# USBSocket_Type4_v1_0.net
KiCad netlist of a schematic drawn in EAGLE
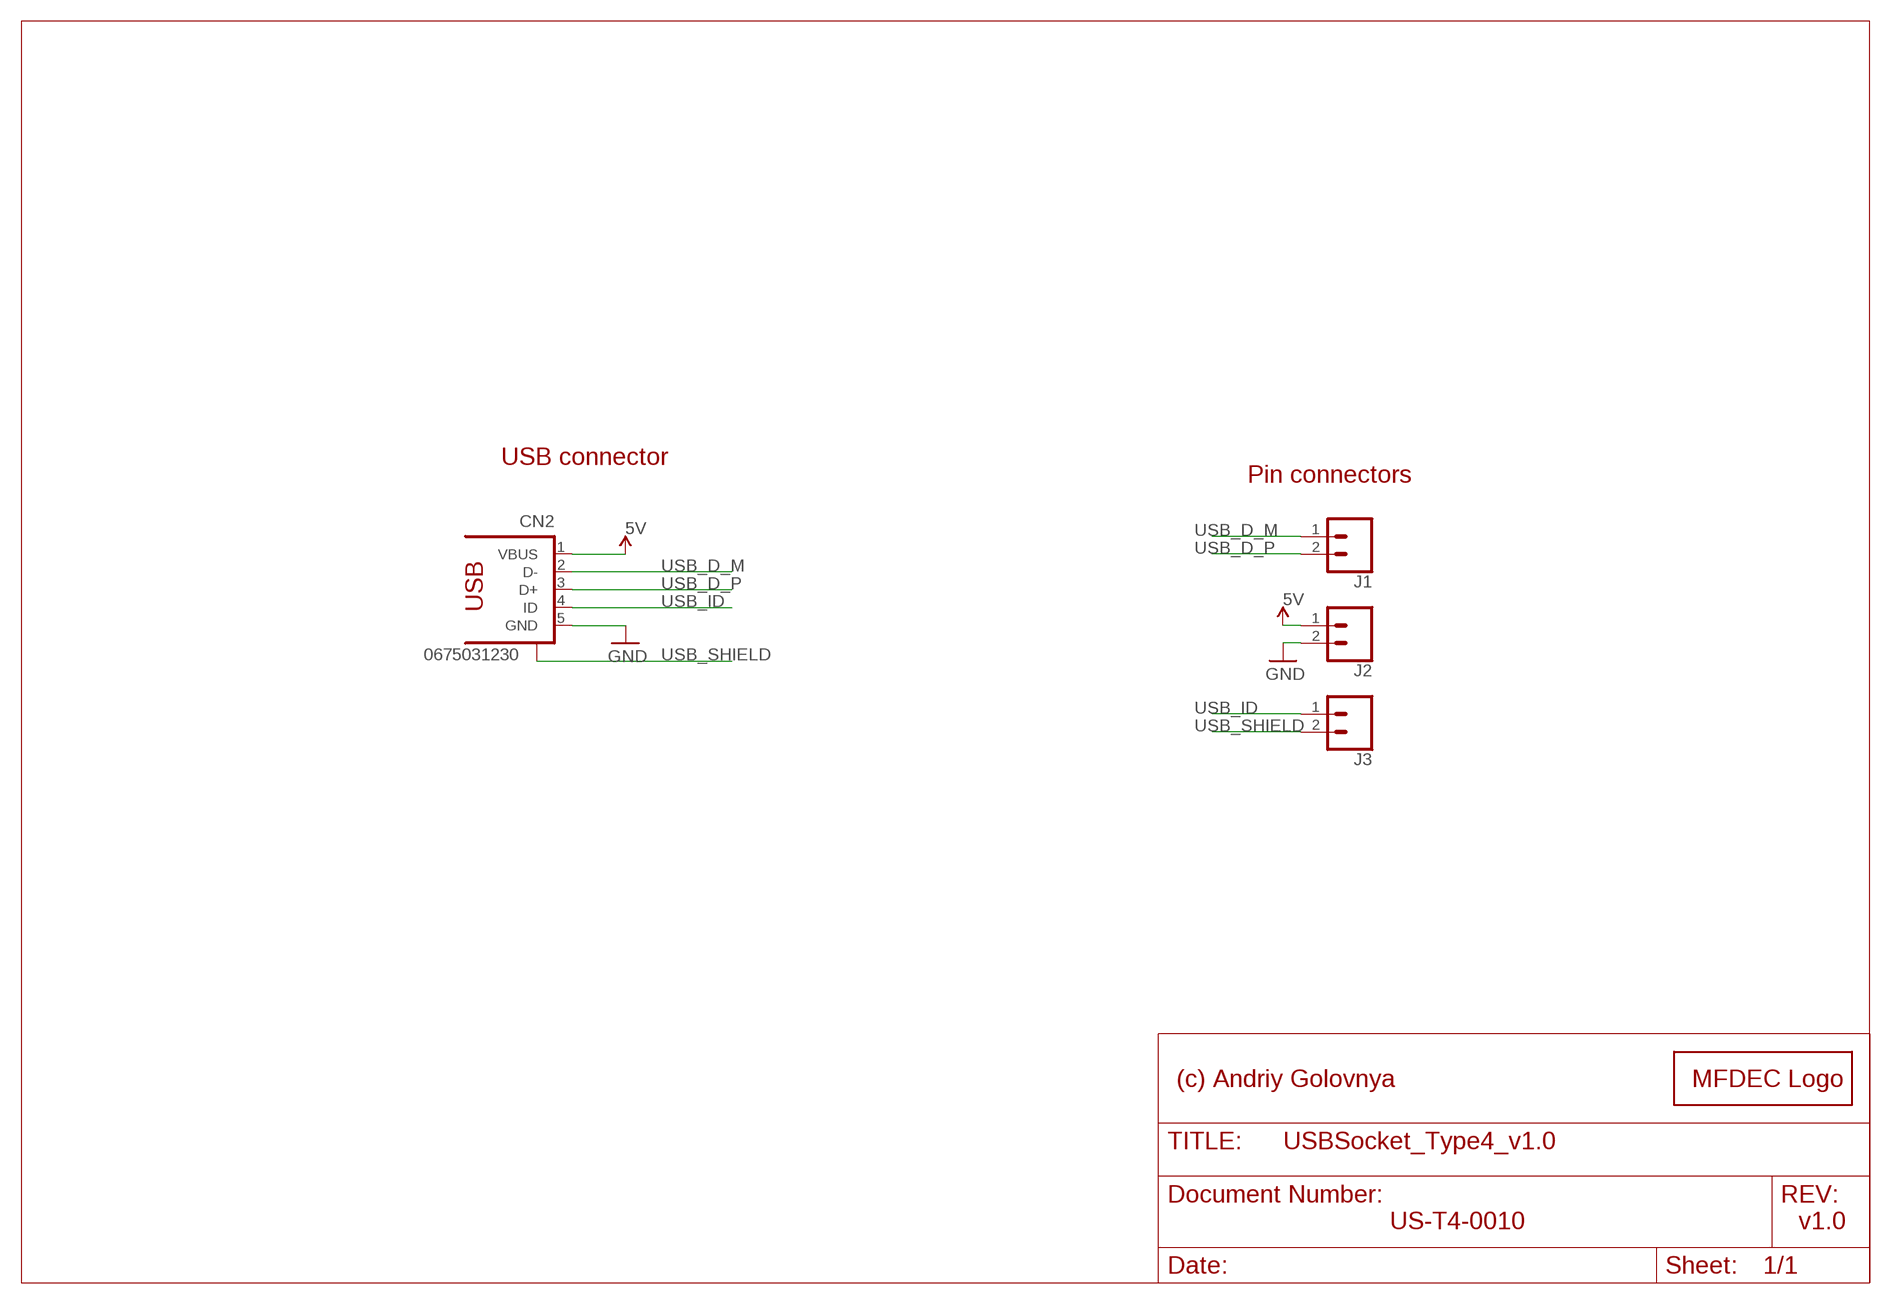
[diagram p0: schematic, sheet 1]

(export (version "E")
  (design (tool "Eeschema 10.0.6"))
  (components
    (comp (ref "CN2")
      (value "0675031230")
      (footprint "eagle-import:PMX42_56579-0576")
      (libsource (lib "eagle-import") (part "PMX42_56579-0576"))
    )
    (comp (ref "J1")
      (value "CONN_02")
      (footprint "eagle-import:1X02")
      (libsource (lib "eagle-import") (part "CONN_02"))
    )
    (comp (ref "J2")
      (value "CONN_02")
      (footprint "eagle-import:1X02")
      (libsource (lib "eagle-import") (part "CONN_02"))
    )
    (comp (ref "J3")
      (value "CONN_02")
      (footprint "eagle-import:1X02")
      (libsource (lib "eagle-import") (part "CONN_02"))
    )
    (comp (ref "LOGO1")
      (value "MFDECLOGO_L_10MM")
      (footprint "eagle-import:MFDEC_L_10MM")
      (libsource (lib "eagle-import") (part "MFDECLOGO_L_10MM"))
    )
  )
  (nets
    (net (code "1") (name "/USB_D_M") (class "Default")
      (node (ref "CN2") (pin "2") (pinfunction "D-_2") (pintype "passive"))
      (node (ref "J1") (pin "1") (pinfunction "1_1") (pintype "passive"))
    )
    (net (code "2") (name "/USB_D_P") (class "Default")
      (node (ref "CN2") (pin "3") (pinfunction "D+_3") (pintype "passive"))
      (node (ref "J1") (pin "2") (pinfunction "2_2") (pintype "passive"))
    )
    (net (code "3") (name "/USB_ID") (class "Default")
      (node (ref "CN2") (pin "4") (pinfunction "ID_4") (pintype "passive"))
      (node (ref "J3") (pin "1") (pinfunction "1_1") (pintype "passive"))
    )
    (net (code "4") (name "/USB_SHIELD") (class "Default")
      (node (ref "CN2") (pin "S1") (pinfunction "S_S1") (pintype "passive"))
      (node (ref "CN2") (pin "S2") (pinfunction "S_S2") (pintype "passive"))
      (node (ref "CN2") (pin "S3") (pinfunction "S_S3") (pintype "passive"))
      (node (ref "CN2") (pin "S4") (pinfunction "S_S4") (pintype "passive"))
      (node (ref "J3") (pin "2") (pinfunction "2_2") (pintype "passive"))
    )
    (net (code "5") (name "5V") (class "Default")
      (node (ref "CN2") (pin "1") (pinfunction "VBUS_1") (pintype "passive"))
      (node (ref "J2") (pin "1") (pinfunction "1_1") (pintype "passive"))
    )
    (net (code "6") (name "GND") (class "Default")
      (node (ref "CN2") (pin "5") (pinfunction "GND_5") (pintype "passive"))
      (node (ref "J2") (pin "2") (pinfunction "2_2") (pintype "passive"))
    )
  )
)
